# STM32WL_MCU_IOs.net
KiCad netlist of a schematic drawn in Altium Designer
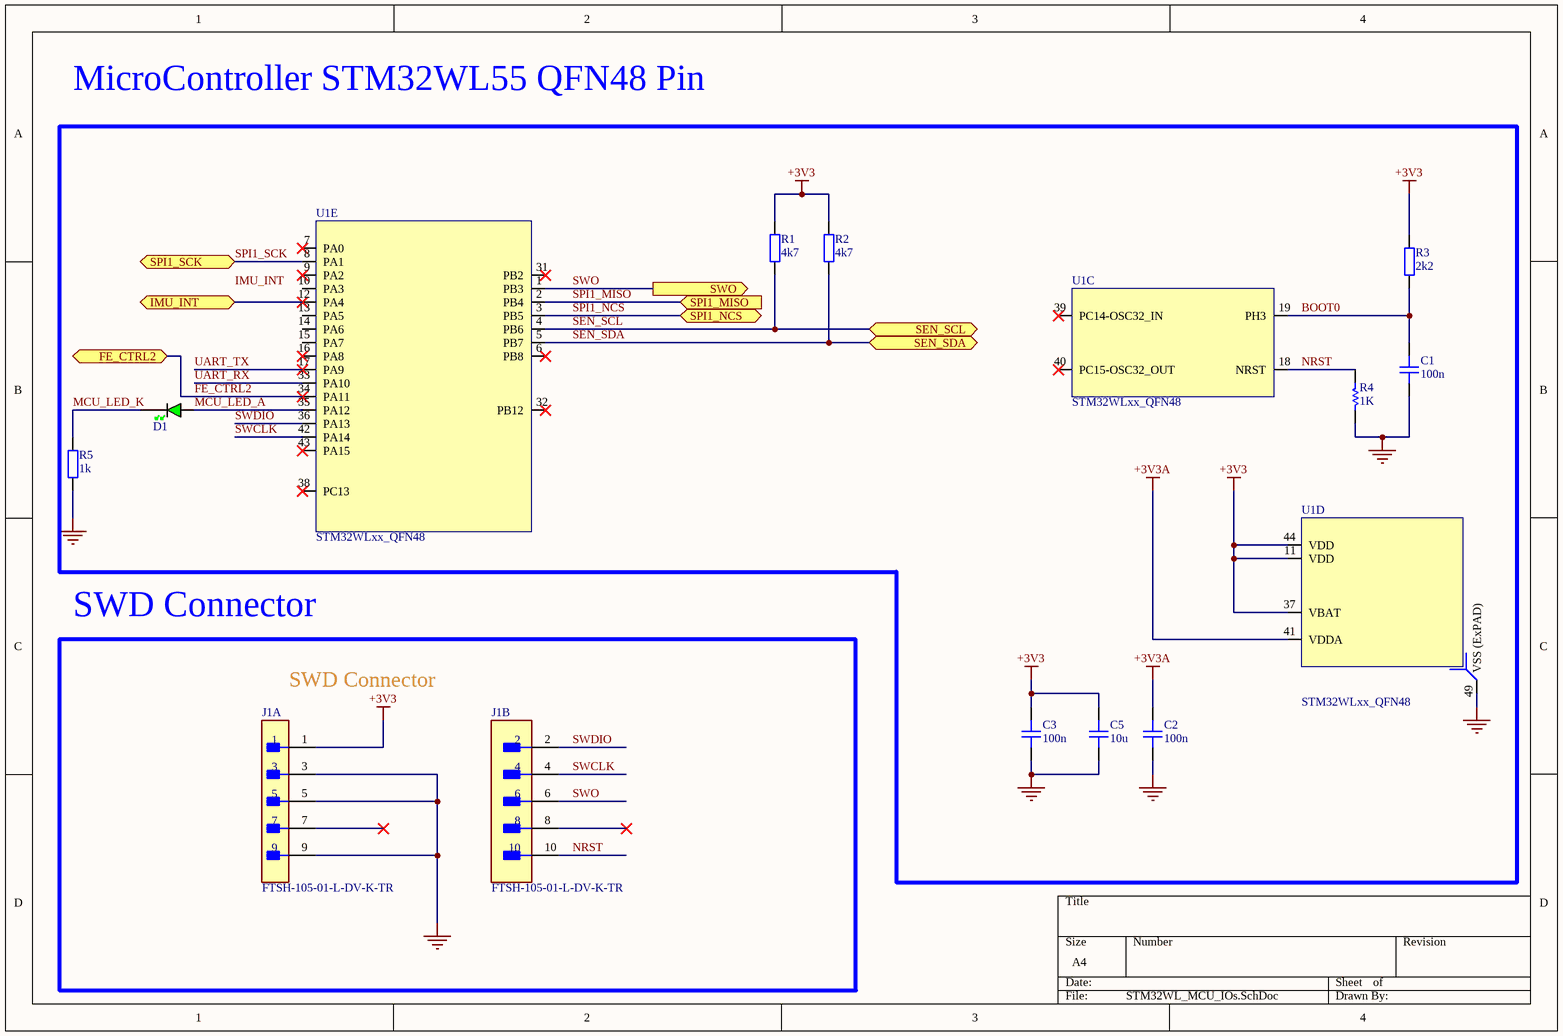
[diagram p0: STM32WL_MCU_IOs.SchDoc]

(export (version "E")
  (design (tool "Eeschema 10.0.6"))
  (components
    (comp (ref "C1")
      (value "100n")
      (footprint "CAP_0603")
      (description "Capacitor SMD 0402 16V")
      (libsource (lib "Schematic-Lib-PhilsLab") (part "CAP_0402_16V"))
    )
    (comp (ref "C2")
      (value "100n")
      (footprint "CAP_0603")
      (description "Capacitor SMD 0201 16V")
      (libsource (lib "Schematic-Lib-PhilsLab") (part "CAP_0201_16V"))
    )
    (comp (ref "C3")
      (value "100n")
      (footprint "CAP_0603")
      (description "Capacitor SMD 0201 16V")
      (libsource (lib "Schematic-Lib-PhilsLab") (part "CAP_0201_16V"))
    )
    (comp (ref "C5")
      (value "10u")
      (footprint "CAP_0603")
      (description "Capacitor SMD 0603 16V")
      (libsource (lib "Schematic-Lib-PhilsLab") (part "CAP_0603_16V"))
    )
    (comp (ref "D1")
      (value "GREEN")
      (footprint "LED_0402_GREEN")
      (description "LED 0402 GREEN SMD")
      (libsource (lib "Schematic-Lib-PhilsLab") (part "LED_0402_GREEN"))
    )
    (comp (ref "J1")
      (value "FTSH-105-01-L-DV-K-TR")
      (footprint "FP-FTSH-105-01-L-DV-K-TR-MFG")
      (description "CONN HEADER SMD 10POS 1.27MM")
      (libsource (lib "Altium Content Vault") (part "cf1cfb4cb1e82ff90bf040e1afc05ac"))
    )
    (comp (ref "R1")
      (value "4k7")
      (footprint "RES_0603")
      (description "Resistor SMD 0603")
      (libsource (lib "Schematic-Lib-PhilsLab") (part "RES_0603"))
    )
    (comp (ref "R2")
      (value "4k7")
      (footprint "RES_0603")
      (description "Resistor SMD 0603")
      (libsource (lib "Schematic-Lib-PhilsLab") (part "RES_0603"))
    )
    (comp (ref "R3")
      (value "2k2")
      (footprint "RES_0402")
      (description "Resistor SMD 0402")
      (libsource (lib "Schematic-Lib-PhilsLab") (part "RES_0402"))
    )
    (comp (ref "R4")
      (value "1K")
      (footprint "RES_0603")
      (description "Resistor,1K,0402,1%,1/16W")
      (fields
        (field (name "INTERNAL_PART_NUMBER") "MCD-00061")
        (field (name "MANUFACTURER_PART_NUMBER") "RC0402FR-071KL")
        (field (name "PROVIDED_BY") "SUBCO")
      )
      (libsource (lib "MCD_PARTS_database") (part "Resistor"))
    )
    (comp (ref "R5")
      (value "1k")
      (footprint "RES_0402")
      (description "Resistor SMD 0402")
      (libsource (lib "Schematic-Lib-PhilsLab") (part "RES_0402"))
    )
    (comp (ref "U1")
      (value "STM32WLxx_QFN48")
      (footprint "STM32WLxx_QFN48")
      (description "HQDC : Verified April, 25 2019")
      (fields
        (field (name "MANUFACTURER") "STMicroelectronics")
        (field (name "MANUFACTURER_PART_NUMBER") "STM32WLE5CC")
      )
      (libsource (lib "MB1789_HP") (part "STM32WLxx_QFN48"))
    )
  )
  (nets
    (net (code "1") (name "+3V3") (class "Default")
      (node (ref "C3") (pin "2") (pinfunction "2_2") (pintype "passive"))
      (node (ref "C5") (pin "2") (pinfunction "2_2") (pintype "passive"))
      (node (ref "J1") (pin "1") (pinfunction "1_1") (pintype "passive"))
      (node (ref "R1") (pin "2") (pinfunction "2_2") (pintype "passive"))
      (node (ref "R2") (pin "2") (pinfunction "2_2") (pintype "passive"))
      (node (ref "R3") (pin "2") (pinfunction "2_2") (pintype "passive"))
      (node (ref "U1") (pin "11") (pinfunction "VDD_11") (pintype "passive"))
      (node (ref "U1") (pin "37") (pinfunction "VBAT_37") (pintype "passive"))
      (node (ref "U1") (pin "44") (pinfunction "VDD_44") (pintype "passive"))
    )
    (net (code "2") (name "+3V3A") (class "Default")
      (node (ref "C2") (pin "2") (pinfunction "2_2") (pintype "passive"))
      (node (ref "U1") (pin "41") (pinfunction "VDDA_41") (pintype "passive"))
    )
    (net (code "3") (name "/BOOT0") (class "Default")
      (node (ref "C1") (pin "2") (pinfunction "2_2") (pintype "passive"))
      (node (ref "R3") (pin "1") (pinfunction "1_1") (pintype "passive"))
      (node (ref "U1") (pin "19") (pinfunction "PH3_19") (pintype "passive"))
    )
    (net (code "4") (name "/FE_CTRL2") (class "Default")
      (node (ref "U1") (pin "34") (pinfunction "PA11_34") (pintype "passive+no_connect"))
    )
    (net (code "5") (name "/IMU_INT") (class "Default")
      (node (ref "U1") (pin "12") (pinfunction "PA4_12") (pintype "passive+no_connect"))
    )
    (net (code "6") (name "/MCU_LED_A") (class "Default")
      (node (ref "D1") (pin "A") (pinfunction "A_A") (pintype "passive"))
      (node (ref "U1") (pin "35") (pinfunction "PA12_35") (pintype "passive"))
    )
    (net (code "7") (name "/MCU_LED_K") (class "Default")
      (node (ref "D1") (pin "K") (pinfunction "K_K") (pintype "passive"))
      (node (ref "R5") (pin "2") (pinfunction "2_2") (pintype "passive"))
    )
    (net (code "8") (name "/NRST") (class "Default")
      (node (ref "J1") (pin "10") (pinfunction "10_10") (pintype "passive"))
      (node (ref "R4") (pin "2") (pinfunction "2_2") (pintype "passive"))
      (node (ref "U1") (pin "18") (pinfunction "NRST_18") (pintype "passive"))
    )
    (net (code "9") (name "/SEN_SCL") (class "Default")
      (node (ref "R1") (pin "1") (pinfunction "1_1") (pintype "passive"))
      (node (ref "U1") (pin "4") (pinfunction "PB6_4") (pintype "passive"))
    )
    (net (code "10") (name "/SEN_SDA") (class "Default")
      (node (ref "R2") (pin "1") (pinfunction "1_1") (pintype "passive"))
      (node (ref "U1") (pin "5") (pinfunction "PB7_5") (pintype "passive"))
    )
    (net (code "11") (name "/SPI1_MISO") (class "Default")
      (node (ref "U1") (pin "2") (pinfunction "PB4_2") (pintype "passive"))
    )
    (net (code "12") (name "/SPI1_NCS") (class "Default")
      (node (ref "U1") (pin "3") (pinfunction "PB5_3") (pintype "passive"))
    )
    (net (code "13") (name "/SPI1_SCK") (class "Default")
      (node (ref "U1") (pin "8") (pinfunction "PA1_8") (pintype "passive"))
    )
    (net (code "14") (name "/SWCLK") (class "Default")
      (node (ref "J1") (pin "4") (pinfunction "4_4") (pintype "passive"))
      (node (ref "U1") (pin "42") (pinfunction "PA14_42") (pintype "passive"))
    )
    (net (code "15") (name "/SWDIO") (class "Default")
      (node (ref "J1") (pin "2") (pinfunction "2_2") (pintype "passive"))
      (node (ref "U1") (pin "36") (pinfunction "PA13_36") (pintype "passive"))
    )
    (net (code "16") (name "/SWO") (class "Default")
      (node (ref "J1") (pin "6") (pinfunction "6_6") (pintype "passive"))
      (node (ref "U1") (pin "1") (pinfunction "PB3_1") (pintype "passive"))
    )
    (net (code "17") (name "/UART_RX") (class "Default")
      (node (ref "U1") (pin "33") (pinfunction "PA10_33") (pintype "passive"))
    )
    (net (code "18") (name "/UART_TX") (class "Default")
      (node (ref "U1") (pin "17") (pinfunction "PA9_17") (pintype "passive+no_connect"))
    )
    (net (code "19") (name "GND") (class "Default")
      (node (ref "C1") (pin "1") (pinfunction "1_1") (pintype "passive"))
      (node (ref "C2") (pin "1") (pinfunction "1_1") (pintype "passive"))
      (node (ref "C3") (pin "1") (pinfunction "1_1") (pintype "passive"))
      (node (ref "C5") (pin "1") (pinfunction "1_1") (pintype "passive"))
      (node (ref "J1") (pin "3") (pinfunction "3_3") (pintype "passive"))
      (node (ref "J1") (pin "5") (pinfunction "5_5") (pintype "passive"))
      (node (ref "J1") (pin "9") (pinfunction "9_9") (pintype "passive"))
      (node (ref "R4") (pin "1") (pinfunction "1_1") (pintype "passive"))
      (node (ref "R5") (pin "1") (pinfunction "1_1") (pintype "passive"))
      (node (ref "U1") (pin "49") (pinfunction "VSS_(ExPAD)_49") (pintype "passive"))
    )
    (net (code "20") (name "unconnected-(J1-Pad7)") (class "Default")
      (node (ref "J1") (pin "7") (pinfunction "7_7") (pintype "passive+no_connect"))
    )
    (net (code "21") (name "unconnected-(J1-Pad8)") (class "Default")
      (node (ref "J1") (pin "8") (pinfunction "8_8") (pintype "passive+no_connect"))
    )
    (net (code "22") (name "unconnected-(U1C-PC14-OSC32_IN-Pad39)") (class "Default")
      (node (ref "U1") (pin "39") (pinfunction "PC14-OSC32_IN_39") (pintype "passive+no_connect"))
    )
    (net (code "23") (name "unconnected-(U1C-PC15-OSC32_OUT-Pad40)") (class "Default")
      (node (ref "U1") (pin "40") (pinfunction "PC15-OSC32_OUT_40") (pintype "passive+no_connect"))
    )
    (net (code "24") (name "unconnected-(U1E-PA0-Pad7)") (class "Default")
      (node (ref "U1") (pin "7") (pinfunction "PA0_7") (pintype "passive+no_connect"))
    )
    (net (code "25") (name "unconnected-(U1E-PA2-Pad9)") (class "Default")
      (node (ref "U1") (pin "9") (pinfunction "PA2_9") (pintype "passive+no_connect"))
    )
    (net (code "26") (name "unconnected-(U1E-PA3-Pad10)") (class "Default")
      (node (ref "U1") (pin "10") (pinfunction "PA3_10") (pintype "passive"))
    )
    (net (code "27") (name "unconnected-(U1E-PA5-Pad13)") (class "Default")
      (node (ref "U1") (pin "13") (pinfunction "PA5_13") (pintype "passive"))
    )
    (net (code "28") (name "unconnected-(U1E-PA6-Pad14)") (class "Default")
      (node (ref "U1") (pin "14") (pinfunction "PA6_14") (pintype "passive"))
    )
    (net (code "29") (name "unconnected-(U1E-PA7-Pad15)") (class "Default")
      (node (ref "U1") (pin "15") (pinfunction "PA7_15") (pintype "passive"))
    )
    (net (code "30") (name "unconnected-(U1E-PA8-Pad16)") (class "Default")
      (node (ref "U1") (pin "16") (pinfunction "PA8_16") (pintype "passive+no_connect"))
    )
    (net (code "31") (name "unconnected-(U1E-PA15-Pad43)") (class "Default")
      (node (ref "U1") (pin "43") (pinfunction "PA15_43") (pintype "passive+no_connect"))
    )
    (net (code "32") (name "unconnected-(U1E-PB2-Pad31)") (class "Default")
      (node (ref "U1") (pin "31") (pinfunction "PB2_31") (pintype "passive+no_connect"))
    )
    (net (code "33") (name "unconnected-(U1E-PB8-Pad6)") (class "Default")
      (node (ref "U1") (pin "6") (pinfunction "PB8_6") (pintype "passive+no_connect"))
    )
    (net (code "34") (name "unconnected-(U1E-PB12-Pad32)") (class "Default")
      (node (ref "U1") (pin "32") (pinfunction "PB12_32") (pintype "passive+no_connect"))
    )
    (net (code "35") (name "unconnected-(U1E-PC13-Pad38)") (class "Default")
      (node (ref "U1") (pin "38") (pinfunction "PC13_38") (pintype "passive+no_connect"))
    )
  )
)
